# SCH_PCB_Crescent_Moon_2025-11-14.net
KiCad netlist of a schematic drawn in EasyEDA
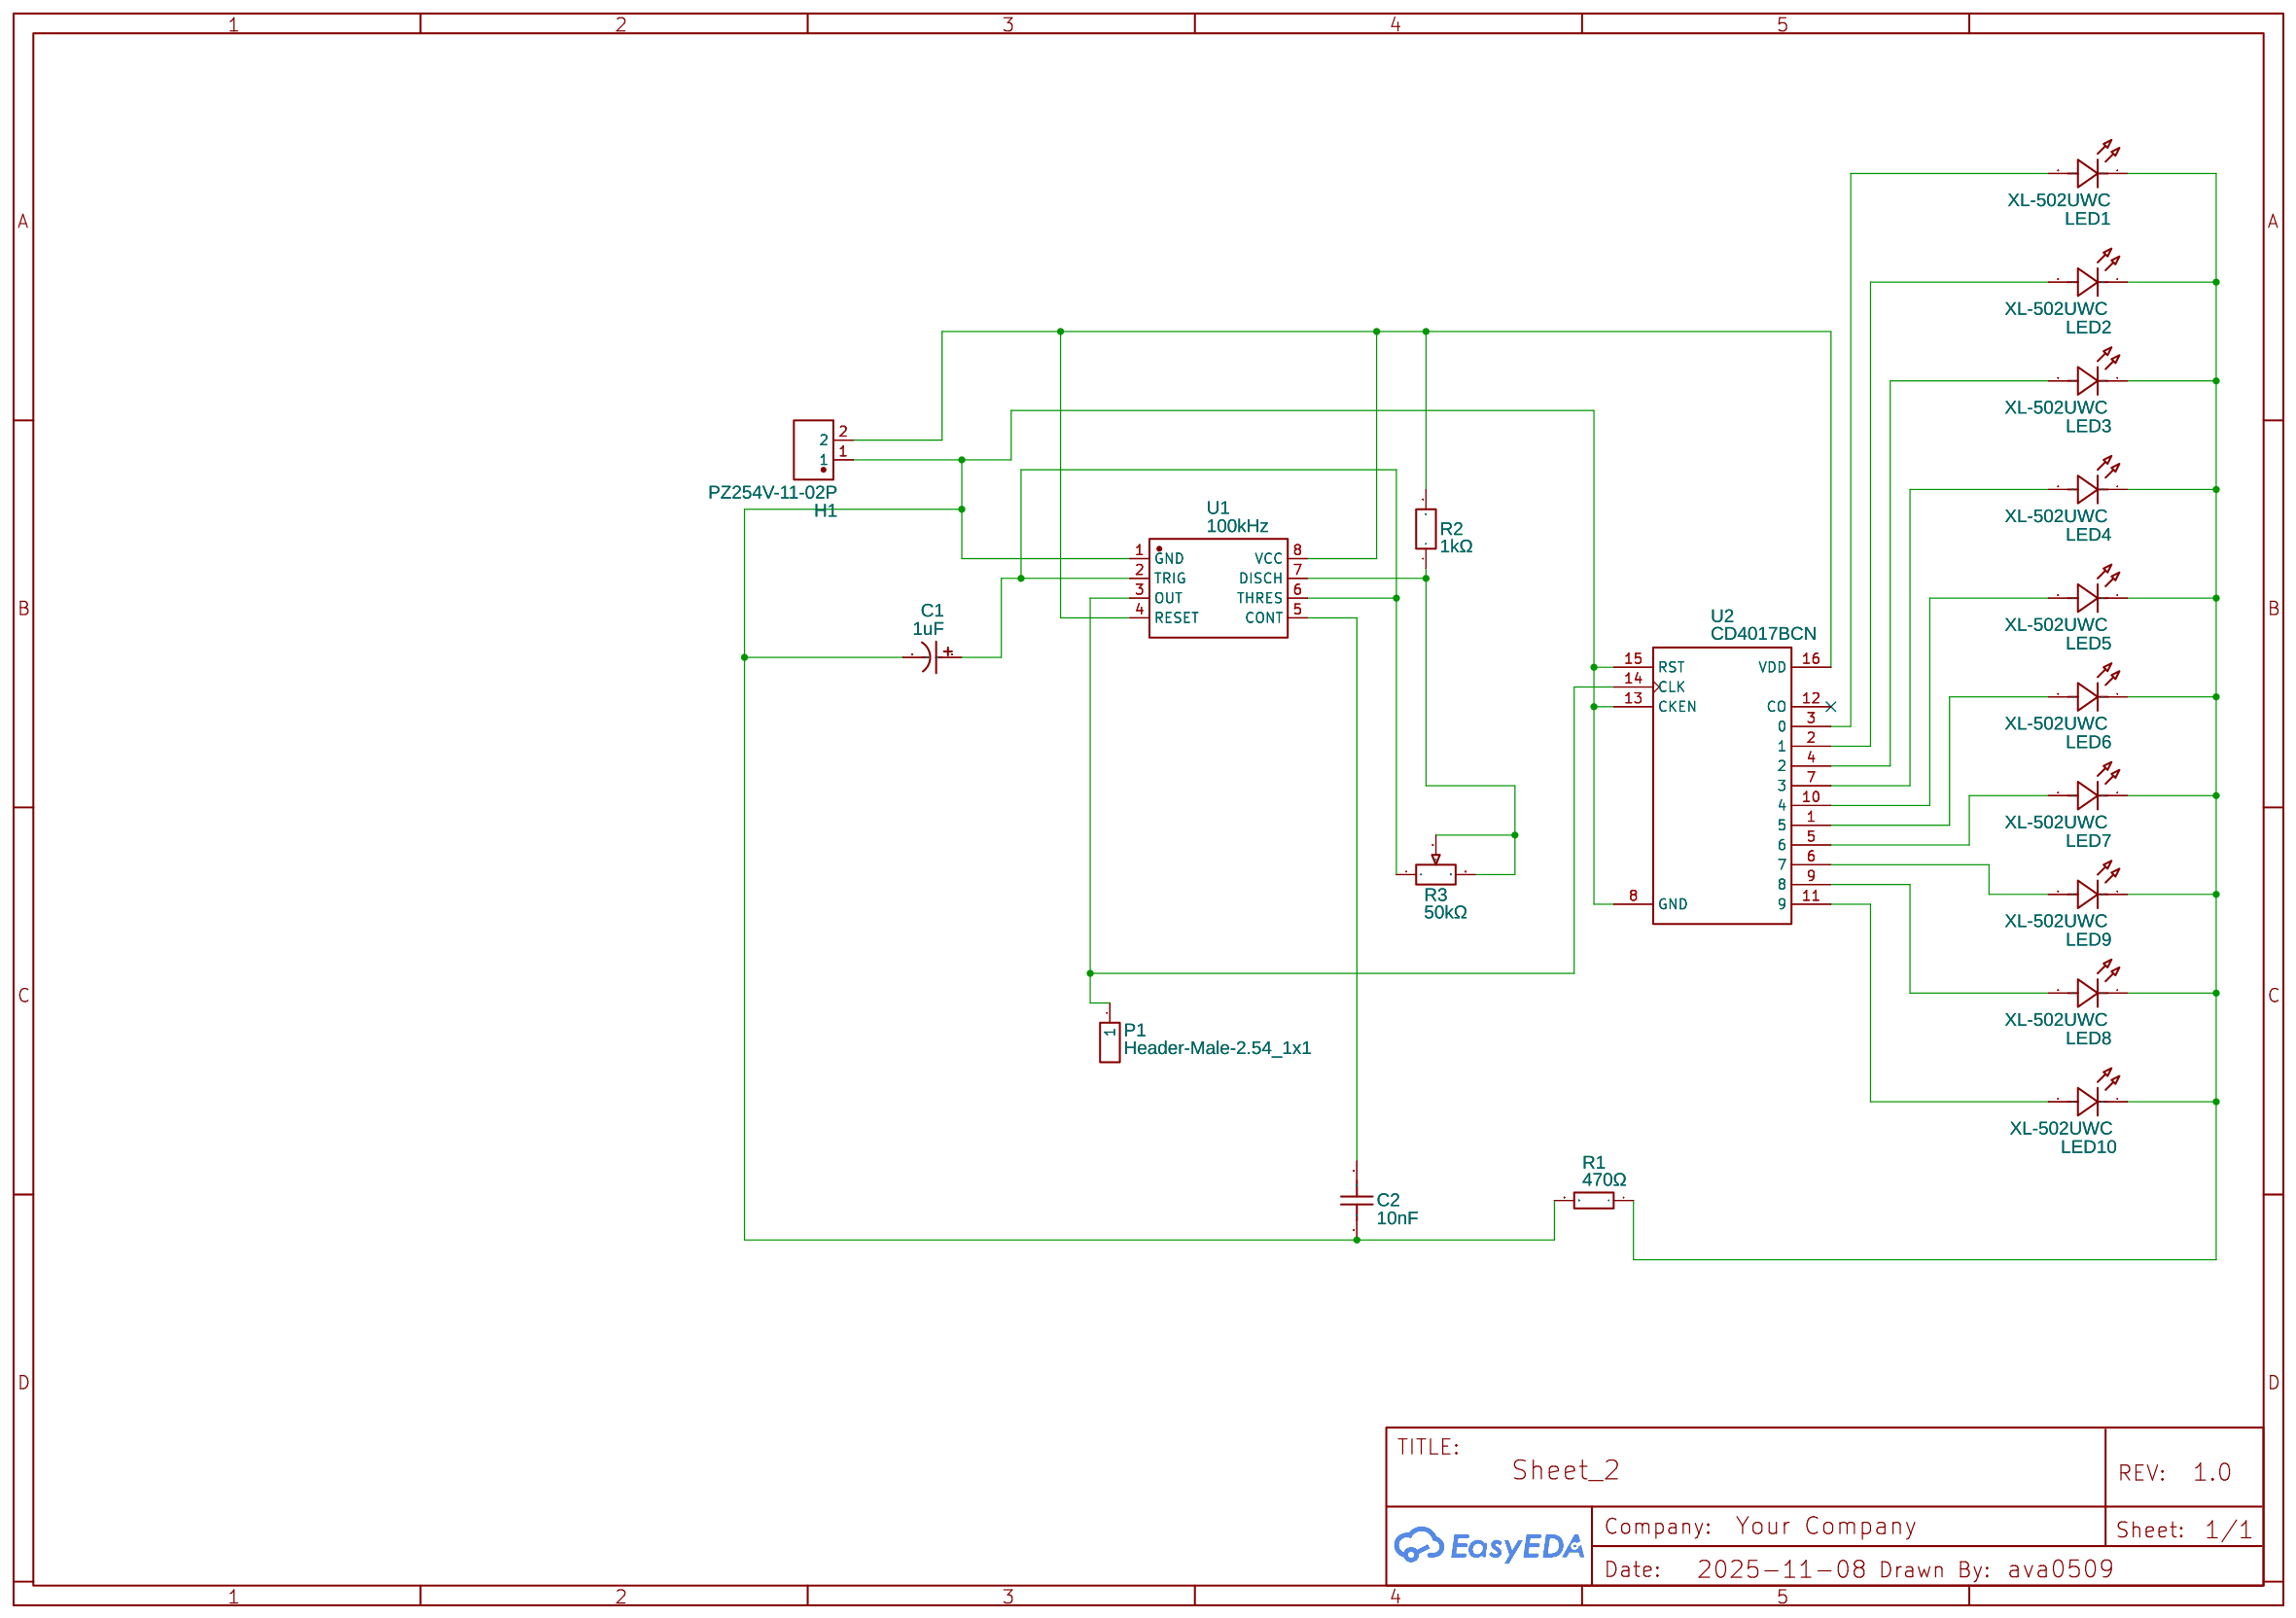
[diagram p0: schematic sheet]

(export (version "E")
  (design (tool "Eeschema 10.0.6"))
  (components
    (comp (ref "C1")
      (value "1uF")
      (fields (field (name "Manufacturer Part") "KF010M050C110A") (field (name "Manufacturer") "CapXon(丰宾)"))
      (libsource (lib "") (part "KF010M050C110A"))
    )
    (comp (ref "C2")
      (value "10nF")
      (fields (field (name "Manufacturer Part") "N09F1B103MN0B0S0N0") (field (name "Manufacturer") "STE(松田)"))
      (libsource (lib "") (part "N09F1B103MN0B0S0N0"))
    )
    (comp (ref "H1")
      (value "PZ254V-11-02P")
      (fields (field (name "Manufacturer") "XFCN(兴飞)"))
      (libsource (lib "") (part "PZ254V-11-02P"))
    )
    (comp (ref "LED1")
      (value "XL-502UWC")
      (fields (field (name "Manufacturer") "XINGLIGHT(成兴光)"))
      (libsource (lib "") (part "XL-502UWC"))
    )
    (comp (ref "LED2")
      (value "XL-502UWC")
      (fields (field (name "Manufacturer") "XINGLIGHT(成兴光)"))
      (libsource (lib "") (part "XL-502UWC"))
    )
    (comp (ref "LED3")
      (value "XL-502UWC")
      (fields (field (name "Manufacturer") "XINGLIGHT(成兴光)"))
      (libsource (lib "") (part "XL-502UWC"))
    )
    (comp (ref "LED4")
      (value "XL-502UWC")
      (fields (field (name "Manufacturer") "XINGLIGHT(成兴光)"))
      (libsource (lib "") (part "XL-502UWC"))
    )
    (comp (ref "LED5")
      (value "XL-502UWC")
      (fields (field (name "Manufacturer") "XINGLIGHT(成兴光)"))
      (libsource (lib "") (part "XL-502UWC"))
    )
    (comp (ref "LED6")
      (value "XL-502UWC")
      (fields (field (name "Manufacturer") "XINGLIGHT(成兴光)"))
      (libsource (lib "") (part "XL-502UWC"))
    )
    (comp (ref "LED7")
      (value "XL-502UWC")
      (fields (field (name "Manufacturer") "XINGLIGHT(成兴光)"))
      (libsource (lib "") (part "XL-502UWC"))
    )
    (comp (ref "LED8")
      (value "XL-502UWC")
      (fields (field (name "Manufacturer") "XINGLIGHT(成兴光)"))
      (libsource (lib "") (part "XL-502UWC"))
    )
    (comp (ref "LED9")
      (value "XL-502UWC")
      (fields (field (name "Manufacturer") "XINGLIGHT(成兴光)"))
      (libsource (lib "") (part "XL-502UWC"))
    )
    (comp (ref "LED10")
      (value "XL-502UWC")
      (fields (field (name "Manufacturer") "XINGLIGHT(成兴光)"))
      (libsource (lib "") (part "XL-502UWC"))
    )
    (comp (ref "P1")
      (value "Header-Male-2.54_1x1")
      (fields (field (name "Manufacturer Part") "2.54-1*1P针") (field (name "Manufacturer") "BOOMELE(博穆精密)"))
      (libsource (lib "") (part "Header-Male-2.54_1x1"))
    )
    (comp (ref "R1")
      (value "470Ω")
      (fields
        (field (name "Manufacturer Part") "MFR0W4F4700A50")
        (field (name "Manufacturer") "UNI-ROYAL(厚声)")
      )
      (libsource (lib "") (part "MFR0W4F4700A50"))
    )
    (comp (ref "R2")
      (value "1kΩ")
      (fields (field (name "Manufacturer Part") "MF1/4W-1KΩ±1%T52") (field (name "Manufacturer") "华星机电"))
      (libsource (lib "") (part "MF1/4W-1KΩ±1%T52"))
    )
    (comp (ref "R3")
      (value "50kΩ")
      (fields (field (name "Manufacturer Part") "3296X-1-503") (field (name "Manufacturer") "BOCHEN(博晨)"))
      (libsource (lib "") (part "3296X-1-503_C118912"))
    )
    (comp (ref "U1")
      (value "100kHz")
      (fields (field (name "Manufacturer Part") "NE555P") (field (name "Manufacturer") "TI(德州仪器)"))
      (libsource (lib "") (part "NE555P"))
    )
    (comp (ref "U2") (value "CD4017BCN") (libsource (lib "") (part "CD4017BCN")))
  )
  (nets
    (net (code "1") (name "Net-(LED1-A)") (class "Default")
      (node (ref "LED1") (pin "2") (pinfunction "A_2") (pintype "unspecified"))
      (node (ref "U2") (pin "3") (pinfunction "0_3") (pintype "output"))
    )
    (net (code "2") (name "Net-(LED1-K)") (class "Default")
      (node (ref "LED1") (pin "1") (pinfunction "K_1") (pintype "unspecified"))
      (node (ref "LED10") (pin "1") (pinfunction "K_1") (pintype "unspecified"))
      (node (ref "LED2") (pin "1") (pinfunction "K_1") (pintype "unspecified"))
      (node (ref "LED3") (pin "1") (pinfunction "K_1") (pintype "unspecified"))
      (node (ref "LED4") (pin "1") (pinfunction "K_1") (pintype "unspecified"))
      (node (ref "LED5") (pin "1") (pinfunction "K_1") (pintype "unspecified"))
      (node (ref "LED6") (pin "1") (pinfunction "K_1") (pintype "unspecified"))
      (node (ref "LED7") (pin "1") (pinfunction "K_1") (pintype "unspecified"))
      (node (ref "LED8") (pin "1") (pinfunction "K_1") (pintype "unspecified"))
      (node (ref "LED9") (pin "1") (pinfunction "K_1") (pintype "unspecified"))
      (node (ref "R1") (pin "1") (pinfunction "1_1") (pintype "input"))
    )
    (net (code "3") (name "Net-(LED2-A)") (class "Default")
      (node (ref "LED2") (pin "2") (pinfunction "A_2") (pintype "unspecified"))
      (node (ref "U2") (pin "2") (pinfunction "1_2") (pintype "output"))
    )
    (net (code "4") (name "Net-(LED3-A)") (class "Default")
      (node (ref "LED3") (pin "2") (pinfunction "A_2") (pintype "unspecified"))
      (node (ref "U2") (pin "4") (pinfunction "2_4") (pintype "output"))
    )
    (net (code "5") (name "Net-(LED4-A)") (class "Default")
      (node (ref "LED4") (pin "2") (pinfunction "A_2") (pintype "unspecified"))
      (node (ref "U2") (pin "7") (pinfunction "3_7") (pintype "output"))
    )
    (net (code "6") (name "Net-(LED5-A)") (class "Default")
      (node (ref "LED5") (pin "2") (pinfunction "A_2") (pintype "unspecified"))
      (node (ref "U2") (pin "10") (pinfunction "4_10") (pintype "output"))
    )
    (net (code "7") (name "Net-(LED6-A)") (class "Default")
      (node (ref "LED6") (pin "2") (pinfunction "A_2") (pintype "unspecified"))
      (node (ref "U2") (pin "1") (pinfunction "5_1") (pintype "output"))
    )
    (net (code "8") (name "Net-(LED7-A)") (class "Default")
      (node (ref "LED7") (pin "2") (pinfunction "A_2") (pintype "unspecified"))
      (node (ref "U2") (pin "5") (pinfunction "6_5") (pintype "output"))
    )
    (net (code "9") (name "Net-(LED8-A)") (class "Default")
      (node (ref "LED8") (pin "2") (pinfunction "A_2") (pintype "unspecified"))
      (node (ref "U2") (pin "9") (pinfunction "8_9") (pintype "output"))
    )
    (net (code "10") (name "Net-(LED9-A)") (class "Default")
      (node (ref "LED9") (pin "2") (pinfunction "A_2") (pintype "unspecified"))
      (node (ref "U2") (pin "6") (pinfunction "7_6") (pintype "output"))
    )
    (net (code "11") (name "Net-(LED10-A)") (class "Default")
      (node (ref "LED10") (pin "2") (pinfunction "A_2") (pintype "unspecified"))
      (node (ref "U2") (pin "11") (pinfunction "9_11") (pintype "output"))
    )
    (net (code "12") (name "Net-(U1-CONT)") (class "Default")
      (node (ref "C2") (pin "2") (pinfunction "2_2") (pintype "unspecified"))
      (node (ref "U1") (pin "5") (pinfunction "CONT_5") (pintype "unspecified"))
    )
    (net (code "13") (name "Net-(U1-DISCH)") (class "Default")
      (node (ref "R2") (pin "1") (pinfunction "1_1") (pintype "unspecified"))
      (node (ref "R3") (pin "2") (pinfunction "2_2") (pintype "input"))
      (node (ref "R3") (pin "3") (pinfunction "3_3") (pintype "input"))
      (node (ref "U1") (pin "7") (pinfunction "DISCH_7") (pintype "unspecified"))
    )
    (net (code "14") (name "Net-(U1-GND)") (class "Default")
      (node (ref "C1") (pin "2") (pinfunction "2_2") (pintype "input"))
      (node (ref "C2") (pin "1") (pinfunction "1_1") (pintype "unspecified"))
      (node (ref "H1") (pin "1") (pinfunction "1_1") (pintype "unspecified"))
      (node (ref "R1") (pin "2") (pinfunction "2_2") (pintype "input"))
      (node (ref "U1") (pin "1") (pinfunction "GND_1") (pintype "unspecified"))
      (node (ref "U2") (pin "13") (pinfunction "CKEN_13") (pintype "unspecified"))
      (node (ref "U2") (pin "15") (pinfunction "RST_15") (pintype "unspecified"))
      (node (ref "U2") (pin "8") (pinfunction "GND_8") (pintype "passive"))
    )
    (net (code "15") (name "Net-(U1-OUT)") (class "Default")
      (node (ref "P1") (pin "1") (pinfunction "1_1") (pintype "input"))
      (node (ref "U1") (pin "3") (pinfunction "OUT_3") (pintype "unspecified"))
      (node (ref "U2") (pin "14") (pinfunction "CLK_14") (pintype "unspecified"))
    )
    (net (code "16") (name "Net-(U1-RESET)") (class "Default")
      (node (ref "H1") (pin "2") (pinfunction "2_2") (pintype "unspecified"))
      (node (ref "R2") (pin "2") (pinfunction "2_2") (pintype "unspecified"))
      (node (ref "U1") (pin "4") (pinfunction "RESET_4") (pintype "unspecified"))
      (node (ref "U1") (pin "8") (pinfunction "VCC_8") (pintype "unspecified"))
      (node (ref "U2") (pin "16") (pinfunction "VDD_16") (pintype "passive"))
    )
    (net (code "17") (name "Net-(U1-THRES)") (class "Default")
      (node (ref "C1") (pin "1") (pinfunction "1_1") (pintype "input"))
      (node (ref "R3") (pin "1") (pinfunction "1_1") (pintype "input"))
      (node (ref "U1") (pin "2") (pinfunction "TRIG_2") (pintype "unspecified"))
      (node (ref "U1") (pin "6") (pinfunction "THRES_6") (pintype "unspecified"))
    )
    (net (code "18") (name "unconnected-(U2-CO-Pad12)") (class "Default")
      (node (ref "U2") (pin "12") (pinfunction "CO_12") (pintype "output+no_connect"))
    )
  )
)
